# i2c2lcd.net
KiCad netlist of a schematic drawn in EAGLE
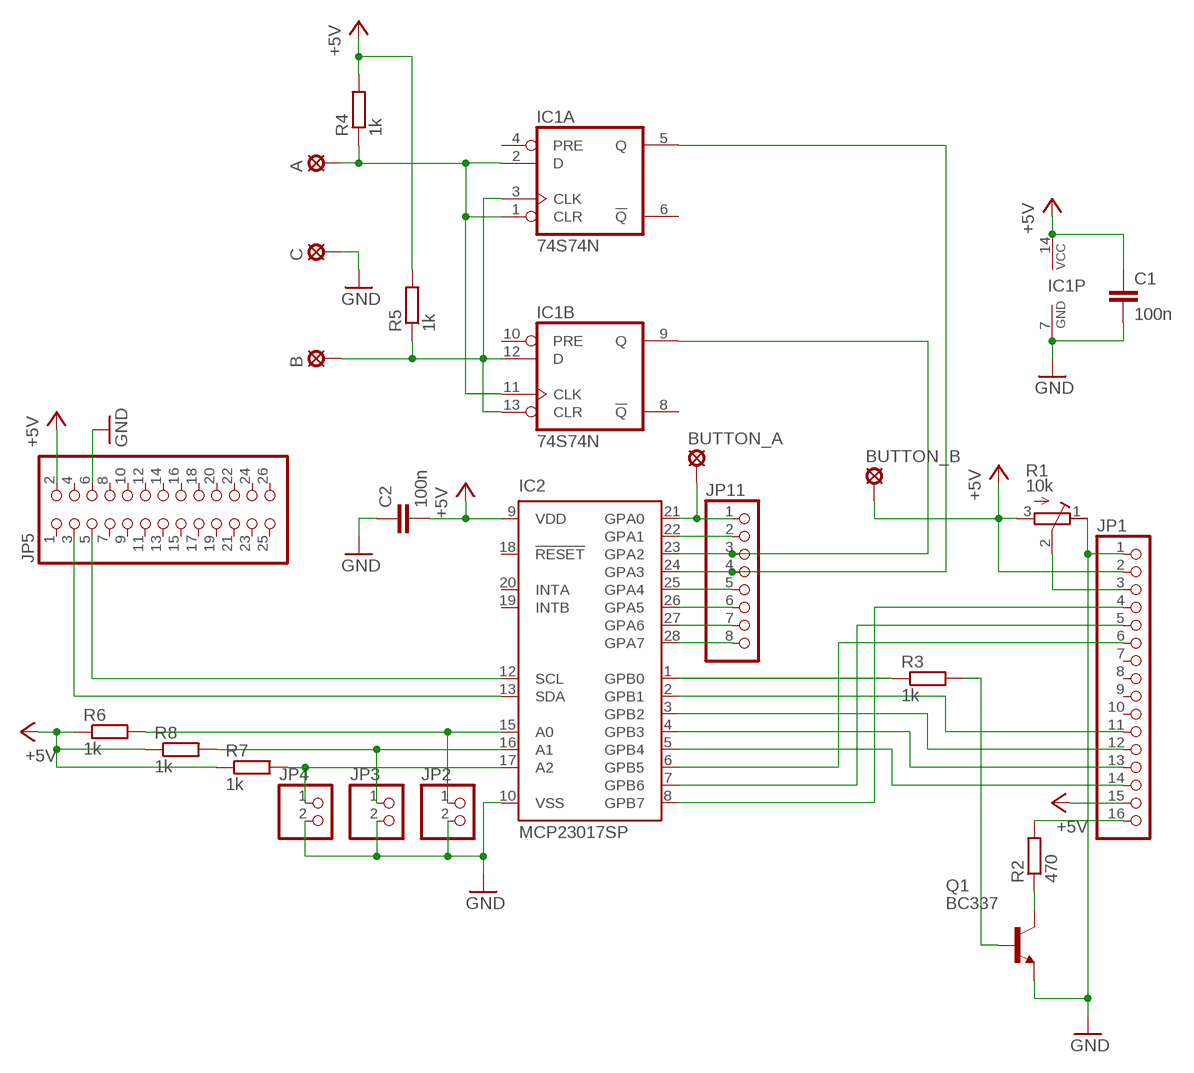
[diagram p0: schematic, sheet 1]

(export (version "E")
  (design (tool "Eeschema 10.0.6"))
  (components
    (comp (ref "A")
      (value "LSP13")
      (footprint "eagle-import:LSP13")
      (libsource (lib "eagle-import") (part "LSP13"))
    )
    (comp (ref "B")
      (value "LSP13")
      (footprint "eagle-import:LSP13")
      (libsource (lib "eagle-import") (part "LSP13"))
    )
    (comp (ref "BUTTON_A")
      (value "LSP13")
      (footprint "eagle-import:LSP13")
      (libsource (lib "eagle-import") (part "LSP13"))
    )
    (comp (ref "BUTTON_B")
      (value "LSP13")
      (footprint "eagle-import:LSP13")
      (libsource (lib "eagle-import") (part "LSP13"))
    )
    (comp (ref "C")
      (value "LSP13")
      (footprint "eagle-import:LSP13")
      (libsource (lib "eagle-import") (part "LSP13"))
    )
    (comp (ref "C1")
      (value "100n")
      (footprint "eagle-import:C1206K")
      (libsource (lib "eagle-import") (part "C-EUC1206K"))
    )
    (comp (ref "C2")
      (value "100n")
      (footprint "eagle-import:C1206K")
      (libsource (lib "eagle-import") (part "C-EUC1206K"))
    )
    (comp (ref "IC1")
      (value "74S74N")
      (footprint "eagle-import:DIL14")
      (libsource (lib "eagle-import") (part "7474NS"))
    )
    (comp (ref "IC2")
      (value "MCP23017SP")
      (footprint "eagle-import:DIL28-3")
      (fields (field (name "MF") "MICROCHIP") (field (name "MPN") "MCP23017-E/SP"))
      (libsource (lib "eagle-import") (part "MCP23017SP"))
    )
    (comp (ref "JP1")
      (value "PINHD-1X16")
      (footprint "eagle-import:1X16")
      (libsource (lib "eagle-import") (part "PINHD-1X16"))
    )
    (comp (ref "JP2")
      (value "PINHD-1X2")
      (footprint "eagle-import:1X02")
      (libsource (lib "eagle-import") (part "PINHD-1X2"))
    )
    (comp (ref "JP3")
      (value "PINHD-1X2")
      (footprint "eagle-import:1X02")
      (libsource (lib "eagle-import") (part "PINHD-1X2"))
    )
    (comp (ref "JP4")
      (value "PINHD-1X2")
      (footprint "eagle-import:1X02")
      (libsource (lib "eagle-import") (part "PINHD-1X2"))
    )
    (comp (ref "JP5")
      (value "PINHD-2X13")
      (footprint "eagle-import:2X13")
      (libsource (lib "eagle-import") (part "PINHD-2X13"))
    )
    (comp (ref "JP11")
      (value "PINHD-1X8")
      (footprint "eagle-import:1X08")
      (libsource (lib "eagle-import") (part "PINHD-1X8"))
    )
    (comp (ref "Q1")
      (value "BC337")
      (footprint "eagle-import:TO92")
      (libsource (lib "eagle-import") (part "BC337"))
    )
    (comp (ref "R1")
      (value "10k")
      (footprint "eagle-import:RTRIM3006P")
      (libsource (lib "eagle-import") (part "R-TRIMM3006P"))
    )
    (comp (ref "R2")
      (value "470")
      (footprint "eagle-import:0207_10")
      (libsource (lib "eagle-import") (part "R-EU_0207/10"))
    )
    (comp (ref "R3")
      (value "1k")
      (footprint "eagle-import:0207_12")
      (libsource (lib "eagle-import") (part "R-EU_0207/12"))
    )
    (comp (ref "R4")
      (value "1k")
      (footprint "eagle-import:0207_10")
      (libsource (lib "eagle-import") (part "R-EU_0207/10"))
    )
    (comp (ref "R5")
      (value "1k")
      (footprint "eagle-import:0207_10")
      (libsource (lib "eagle-import") (part "R-EU_0207/10"))
    )
    (comp (ref "R6")
      (value "1k")
      (footprint "eagle-import:0207_10")
      (libsource (lib "eagle-import") (part "R-EU_0207/10"))
    )
    (comp (ref "R7")
      (value "1k")
      (footprint "eagle-import:0207_10")
      (libsource (lib "eagle-import") (part "R-EU_0207/10"))
    )
    (comp (ref "R8")
      (value "1k")
      (footprint "eagle-import:0207_10")
      (libsource (lib "eagle-import") (part "R-EU_0207/10"))
    )
  )
  (nets
    (net (code "1") (name "+5V") (class "Default")
      (node (ref "BUTTON_B") (pin "MP") (pinfunction "MP_MP") (pintype "passive"))
      (node (ref "C1") (pin "1") (pinfunction "1_1") (pintype "passive"))
      (node (ref "C2") (pin "2") (pinfunction "2_2") (pintype "passive"))
      (node (ref "IC1") (pin "14") (pinfunction "VCC_14") (pintype "power_in"))
      (node (ref "IC2") (pin "9") (pinfunction "VDD_9") (pintype "power_in"))
      (node (ref "JP1") (pin "15") (pinfunction "15_15") (pintype "passive"))
      (node (ref "JP1") (pin "2") (pinfunction "2_2") (pintype "passive"))
      (node (ref "JP5") (pin "2") (pinfunction "2_2") (pintype "passive"))
      (node (ref "R1") (pin "3") (pinfunction "A_3") (pintype "passive"))
      (node (ref "R4") (pin "2") (pinfunction "2_2") (pintype "passive"))
      (node (ref "R5") (pin "2") (pinfunction "2_2") (pintype "passive"))
      (node (ref "R6") (pin "1") (pinfunction "1_1") (pintype "passive"))
      (node (ref "R7") (pin "1") (pinfunction "1_1") (pintype "passive"))
      (node (ref "R8") (pin "1") (pinfunction "1_1") (pintype "passive"))
    )
    (net (code "2") (name "GND") (class "Default")
      (node (ref "C") (pin "MP") (pinfunction "MP_MP") (pintype "passive"))
      (node (ref "C1") (pin "2") (pinfunction "2_2") (pintype "passive"))
      (node (ref "C2") (pin "1") (pinfunction "1_1") (pintype "passive"))
      (node (ref "IC1") (pin "7") (pinfunction "GND_7") (pintype "power_in"))
      (node (ref "IC2") (pin "10") (pinfunction "VSS_10") (pintype "power_in"))
      (node (ref "JP1") (pin "1") (pinfunction "1_1") (pintype "passive"))
      (node (ref "JP2") (pin "2") (pinfunction "2_2") (pintype "passive"))
      (node (ref "JP3") (pin "2") (pinfunction "2_2") (pintype "passive"))
      (node (ref "JP4") (pin "2") (pinfunction "2_2") (pintype "passive"))
      (node (ref "JP5") (pin "6") (pinfunction "6_6") (pintype "passive"))
      (node (ref "Q1") (pin "1") (pinfunction "E_1") (pintype "passive"))
      (node (ref "R1") (pin "1") (pinfunction "E_1") (pintype "passive"))
    )
    (net (code "3") (name "Net-(IC1A-CLK)") (class "Default")
      (node (ref "B") (pin "MP") (pinfunction "MP_MP") (pintype "passive"))
      (node (ref "IC1") (pin "12") (pinfunction "D_12") (pintype "input"))
      (node (ref "IC1") (pin "13") (pinfunction "CLR_13") (pintype "input"))
      (node (ref "IC1") (pin "3") (pinfunction "CLK_3") (pintype "input"))
      (node (ref "R5") (pin "1") (pinfunction "1_1") (pintype "passive"))
    )
    (net (code "4") (name "Net-(IC1A-CLR)") (class "Default")
      (node (ref "A") (pin "MP") (pinfunction "MP_MP") (pintype "passive"))
      (node (ref "IC1") (pin "1") (pinfunction "CLR_1") (pintype "input"))
      (node (ref "IC1") (pin "11") (pinfunction "CLK_11") (pintype "input"))
      (node (ref "IC1") (pin "2") (pinfunction "D_2") (pintype "input"))
      (node (ref "R4") (pin "1") (pinfunction "1_1") (pintype "passive"))
    )
    (net (code "5") (name "Net-(IC1A-Q)") (class "Default")
      (node (ref "IC1") (pin "5") (pinfunction "Q_5") (pintype "output"))
      (node (ref "IC2") (pin "24") (pinfunction "GPA3_24") (pintype "bidirectional"))
      (node (ref "JP11") (pin "4") (pinfunction "4_4") (pintype "passive"))
    )
    (net (code "6") (name "Net-(IC1B-Q)") (class "Default")
      (node (ref "IC1") (pin "9") (pinfunction "Q_9") (pintype "output"))
      (node (ref "IC2") (pin "23") (pinfunction "GPA2_23") (pintype "bidirectional"))
      (node (ref "JP11") (pin "3") (pinfunction "3_3") (pintype "passive"))
    )
    (net (code "7") (name "Net-(IC2-A0)") (class "Default")
      (node (ref "IC2") (pin "15") (pinfunction "A0_15") (pintype "input"))
      (node (ref "JP2") (pin "1") (pinfunction "1_1") (pintype "passive"))
      (node (ref "R6") (pin "2") (pinfunction "2_2") (pintype "passive"))
    )
    (net (code "8") (name "Net-(IC2-A1)") (class "Default")
      (node (ref "IC2") (pin "16") (pinfunction "A1_16") (pintype "input"))
      (node (ref "JP3") (pin "1") (pinfunction "1_1") (pintype "passive"))
      (node (ref "R8") (pin "2") (pinfunction "2_2") (pintype "passive"))
    )
    (net (code "9") (name "Net-(IC2-A2)") (class "Default")
      (node (ref "IC2") (pin "17") (pinfunction "A2_17") (pintype "input"))
      (node (ref "JP4") (pin "1") (pinfunction "1_1") (pintype "passive"))
      (node (ref "R7") (pin "2") (pinfunction "2_2") (pintype "passive"))
    )
    (net (code "10") (name "Net-(IC2-GPA0)") (class "Default")
      (node (ref "BUTTON_A") (pin "MP") (pinfunction "MP_MP") (pintype "passive"))
      (node (ref "IC2") (pin "21") (pinfunction "GPA0_21") (pintype "bidirectional"))
      (node (ref "JP11") (pin "1") (pinfunction "1_1") (pintype "passive"))
    )
    (net (code "11") (name "Net-(IC2-GPA1)") (class "Default")
      (node (ref "IC2") (pin "22") (pinfunction "GPA1_22") (pintype "bidirectional"))
      (node (ref "JP11") (pin "2") (pinfunction "2_2") (pintype "passive"))
    )
    (net (code "12") (name "Net-(IC2-GPA4)") (class "Default")
      (node (ref "IC2") (pin "25") (pinfunction "GPA4_25") (pintype "bidirectional"))
      (node (ref "JP11") (pin "5") (pinfunction "5_5") (pintype "passive"))
    )
    (net (code "13") (name "Net-(IC2-GPA5)") (class "Default")
      (node (ref "IC2") (pin "26") (pinfunction "GPA5_26") (pintype "bidirectional"))
      (node (ref "JP11") (pin "6") (pinfunction "6_6") (pintype "passive"))
    )
    (net (code "14") (name "Net-(IC2-GPA6)") (class "Default")
      (node (ref "IC2") (pin "27") (pinfunction "GPA6_27") (pintype "bidirectional"))
      (node (ref "JP11") (pin "7") (pinfunction "7_7") (pintype "passive"))
    )
    (net (code "15") (name "Net-(IC2-GPA7)") (class "Default")
      (node (ref "IC2") (pin "28") (pinfunction "GPA7_28") (pintype "bidirectional"))
      (node (ref "JP11") (pin "8") (pinfunction "8_8") (pintype "passive"))
    )
    (net (code "16") (name "Net-(IC2-GPB0)") (class "Default")
      (node (ref "IC2") (pin "1") (pinfunction "GPB0_1") (pintype "bidirectional"))
      (node (ref "R3") (pin "1") (pinfunction "1_1") (pintype "passive"))
    )
    (net (code "17") (name "Net-(IC2-GPB1)") (class "Default")
      (node (ref "IC2") (pin "2") (pinfunction "GPB1_2") (pintype "bidirectional"))
      (node (ref "JP1") (pin "11") (pinfunction "11_11") (pintype "passive"))
    )
    (net (code "18") (name "Net-(IC2-GPB2)") (class "Default")
      (node (ref "IC2") (pin "3") (pinfunction "GPB2_3") (pintype "bidirectional"))
      (node (ref "JP1") (pin "12") (pinfunction "12_12") (pintype "passive"))
    )
    (net (code "19") (name "Net-(IC2-GPB3)") (class "Default")
      (node (ref "IC2") (pin "4") (pinfunction "GPB3_4") (pintype "bidirectional"))
      (node (ref "JP1") (pin "13") (pinfunction "13_13") (pintype "passive"))
    )
    (net (code "20") (name "Net-(IC2-GPB4)") (class "Default")
      (node (ref "IC2") (pin "5") (pinfunction "GPB4_5") (pintype "bidirectional"))
      (node (ref "JP1") (pin "14") (pinfunction "14_14") (pintype "passive"))
    )
    (net (code "21") (name "Net-(IC2-GPB5)") (class "Default")
      (node (ref "IC2") (pin "6") (pinfunction "GPB5_6") (pintype "bidirectional"))
      (node (ref "JP1") (pin "6") (pinfunction "6_6") (pintype "passive"))
    )
    (net (code "22") (name "Net-(IC2-GPB6)") (class "Default")
      (node (ref "IC2") (pin "7") (pinfunction "GPB6_7") (pintype "bidirectional"))
      (node (ref "JP1") (pin "5") (pinfunction "5_5") (pintype "passive"))
    )
    (net (code "23") (name "Net-(IC2-GPB7)") (class "Default")
      (node (ref "IC2") (pin "8") (pinfunction "GPB7_8") (pintype "bidirectional"))
      (node (ref "JP1") (pin "4") (pinfunction "4_4") (pintype "passive"))
    )
    (net (code "24") (name "Net-(IC2-SCL)") (class "Default")
      (node (ref "IC2") (pin "12") (pinfunction "SCL_12") (pintype "input"))
      (node (ref "JP5") (pin "5") (pinfunction "5_5") (pintype "passive"))
    )
    (net (code "25") (name "Net-(IC2-SDA)") (class "Default")
      (node (ref "IC2") (pin "13") (pinfunction "SDA_13") (pintype "bidirectional"))
      (node (ref "JP5") (pin "3") (pinfunction "3_3") (pintype "passive"))
    )
    (net (code "26") (name "Net-(JP1-Pad16)") (class "Default")
      (node (ref "JP1") (pin "16") (pinfunction "16_16") (pintype "passive"))
      (node (ref "R2") (pin "2") (pinfunction "2_2") (pintype "passive"))
    )
    (net (code "27") (name "Net-(Q1-B)") (class "Default")
      (node (ref "Q1") (pin "2") (pinfunction "B_2") (pintype "passive"))
      (node (ref "R3") (pin "2") (pinfunction "2_2") (pintype "passive"))
    )
    (net (code "28") (name "Net-(Q1-C)") (class "Default")
      (node (ref "Q1") (pin "3") (pinfunction "C_3") (pintype "passive"))
      (node (ref "R2") (pin "1") (pinfunction "1_1") (pintype "passive"))
    )
    (net (code "29") (name "Net-(R1-S)") (class "Default")
      (node (ref "JP1") (pin "3") (pinfunction "3_3") (pintype "passive"))
      (node (ref "R1") (pin "2") (pinfunction "S_2") (pintype "passive"))
    )
    (net (code "30") (name "unconnected-(IC1A-PRE-Pad4)") (class "Default")
      (node (ref "IC1") (pin "4") (pinfunction "PRE_4") (pintype "input"))
    )
    (net (code "31") (name "unconnected-(IC1A-~{Q}-Pad6)") (class "Default")
      (node (ref "IC1") (pin "6") (pinfunction "~{Q}_6") (pintype "output"))
    )
    (net (code "32") (name "unconnected-(IC1B-PRE-Pad10)") (class "Default")
      (node (ref "IC1") (pin "10") (pinfunction "PRE_10") (pintype "input"))
    )
    (net (code "33") (name "unconnected-(IC1B-~{Q}-Pad8)") (class "Default")
      (node (ref "IC1") (pin "8") (pinfunction "~{Q}_8") (pintype "output"))
    )
    (net (code "34") (name "unconnected-(IC2-INTA-Pad20)") (class "Default")
      (node (ref "IC2") (pin "20") (pinfunction "INTA_20") (pintype "output"))
    )
    (net (code "35") (name "unconnected-(IC2-INTB-Pad19)") (class "Default")
      (node (ref "IC2") (pin "19") (pinfunction "INTB_19") (pintype "output"))
    )
    (net (code "36") (name "unconnected-(IC2-~{RESET}-Pad18)") (class "Default")
      (node (ref "IC2") (pin "18") (pinfunction "~{RESET}_18") (pintype "input"))
    )
    (net (code "37") (name "unconnected-(JP1-Pad7)") (class "Default")
      (node (ref "JP1") (pin "7") (pinfunction "7_7") (pintype "passive"))
    )
    (net (code "38") (name "unconnected-(JP1-Pad8)") (class "Default")
      (node (ref "JP1") (pin "8") (pinfunction "8_8") (pintype "passive"))
    )
    (net (code "39") (name "unconnected-(JP1-Pad9)") (class "Default")
      (node (ref "JP1") (pin "9") (pinfunction "9_9") (pintype "passive"))
    )
    (net (code "40") (name "unconnected-(JP1-Pad10)") (class "Default")
      (node (ref "JP1") (pin "10") (pinfunction "10_10") (pintype "passive"))
    )
    (net (code "41") (name "unconnected-(JP5-Pad1)") (class "Default")
      (node (ref "JP5") (pin "1") (pinfunction "1_1") (pintype "passive"))
    )
    (net (code "42") (name "unconnected-(JP5-Pad4)") (class "Default")
      (node (ref "JP5") (pin "4") (pinfunction "4_4") (pintype "passive"))
    )
    (net (code "43") (name "unconnected-(JP5-Pad7)") (class "Default")
      (node (ref "JP5") (pin "7") (pinfunction "7_7") (pintype "passive"))
    )
    (net (code "44") (name "unconnected-(JP5-Pad8)") (class "Default")
      (node (ref "JP5") (pin "8") (pinfunction "8_8") (pintype "passive"))
    )
    (net (code "45") (name "unconnected-(JP5-Pad9)") (class "Default")
      (node (ref "JP5") (pin "9") (pinfunction "9_9") (pintype "passive"))
    )
    (net (code "46") (name "unconnected-(JP5-Pad10)") (class "Default")
      (node (ref "JP5") (pin "10") (pinfunction "10_10") (pintype "passive"))
    )
    (net (code "47") (name "unconnected-(JP5-Pad11)") (class "Default")
      (node (ref "JP5") (pin "11") (pinfunction "11_11") (pintype "passive"))
    )
    (net (code "48") (name "unconnected-(JP5-Pad12)") (class "Default")
      (node (ref "JP5") (pin "12") (pinfunction "12_12") (pintype "passive"))
    )
    (net (code "49") (name "unconnected-(JP5-Pad13)") (class "Default")
      (node (ref "JP5") (pin "13") (pinfunction "13_13") (pintype "passive"))
    )
    (net (code "50") (name "unconnected-(JP5-Pad14)") (class "Default")
      (node (ref "JP5") (pin "14") (pinfunction "14_14") (pintype "passive"))
    )
    (net (code "51") (name "unconnected-(JP5-Pad15)") (class "Default")
      (node (ref "JP5") (pin "15") (pinfunction "15_15") (pintype "passive"))
    )
    (net (code "52") (name "unconnected-(JP5-Pad16)") (class "Default")
      (node (ref "JP5") (pin "16") (pinfunction "16_16") (pintype "passive"))
    )
    (net (code "53") (name "unconnected-(JP5-Pad17)") (class "Default")
      (node (ref "JP5") (pin "17") (pinfunction "17_17") (pintype "passive"))
    )
    (net (code "54") (name "unconnected-(JP5-Pad18)") (class "Default")
      (node (ref "JP5") (pin "18") (pinfunction "18_18") (pintype "passive"))
    )
    (net (code "55") (name "unconnected-(JP5-Pad19)") (class "Default")
      (node (ref "JP5") (pin "19") (pinfunction "19_19") (pintype "passive"))
    )
    (net (code "56") (name "unconnected-(JP5-Pad20)") (class "Default")
      (node (ref "JP5") (pin "20") (pinfunction "20_20") (pintype "passive"))
    )
    (net (code "57") (name "unconnected-(JP5-Pad21)") (class "Default")
      (node (ref "JP5") (pin "21") (pinfunction "21_21") (pintype "passive"))
    )
    (net (code "58") (name "unconnected-(JP5-Pad22)") (class "Default")
      (node (ref "JP5") (pin "22") (pinfunction "22_22") (pintype "passive"))
    )
    (net (code "59") (name "unconnected-(JP5-Pad23)") (class "Default")
      (node (ref "JP5") (pin "23") (pinfunction "23_23") (pintype "passive"))
    )
    (net (code "60") (name "unconnected-(JP5-Pad24)") (class "Default")
      (node (ref "JP5") (pin "24") (pinfunction "24_24") (pintype "passive"))
    )
    (net (code "61") (name "unconnected-(JP5-Pad25)") (class "Default")
      (node (ref "JP5") (pin "25") (pinfunction "25_25") (pintype "passive"))
    )
    (net (code "62") (name "unconnected-(JP5-Pad26)") (class "Default")
      (node (ref "JP5") (pin "26") (pinfunction "26_26") (pintype "passive"))
    )
  )
)
